# main.net
KiCad netlist of a schematic drawn in Altium Designer
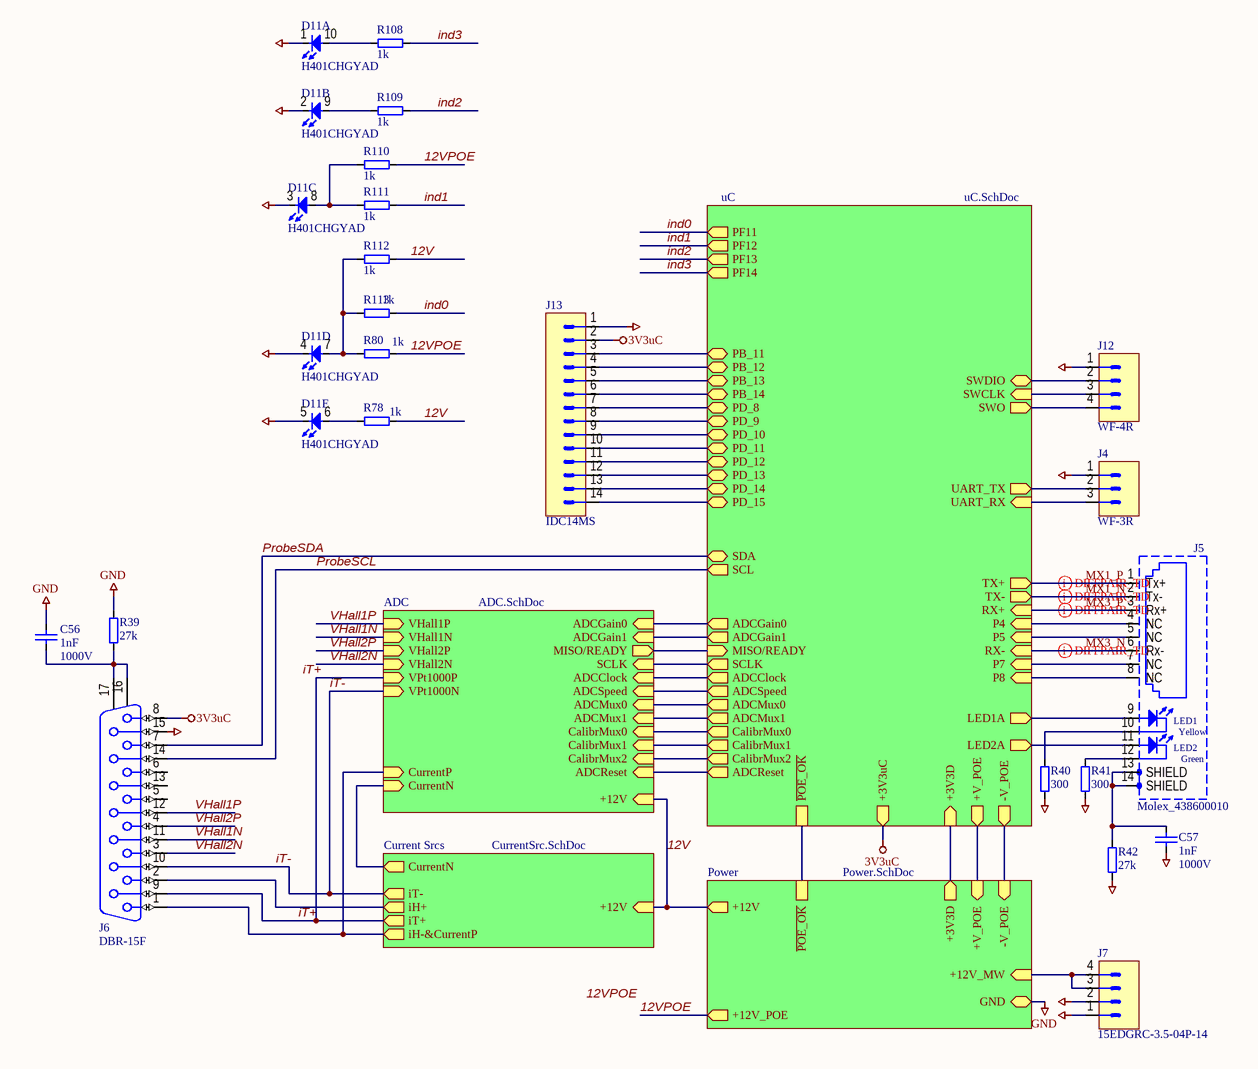
[diagram p0: main.SchDoc]

(export (version "E")
  (design (tool "Eeschema 10.0.6"))
  (components
    (comp (ref "C56")
      (value "1nF")
      (footprint "CAPC1206")
      (description "Чип конденсатор 1206")
      (fields (field (name "VOLTAGE") "1000V") (field (name "TOLERANCE") "1%"))
      (libsource (lib "DDSintLib") (part "C1206"))
    )
    (comp (ref "C57")
      (value "1nF")
      (footprint "CAPC1206")
      (description "Чип конденсатор 1206")
      (fields (field (name "VOLTAGE") "1000V") (field (name "TOLERANCE") "1%"))
      (libsource (lib "DDSintLib") (part "C1206"))
    )
    (comp (ref "D11")
      (value "H401CHGYAD")
      (footprint "H401CHGYAD_LED_CB")
      (description "4LEDs сборка")
      (libsource (lib "DDSintLib") (part "H401CHGYAD"))
    )
    (comp (ref "J4")
      (value "WF-3R")
      (footprint "MOLEX_22-05-7038")
      (description "Вилка  WF3 угловая")
      (libsource (lib "DDSintLib") (part "WF3R"))
    )
    (comp (ref "J5")
      (value "Molex_438600010")
      (footprint "Molex-43860-0010")
      (description "1 Port, 8 Positions, CAT5 RJ45 Modular Connector With Yellow And Green fibers for LEDs")
      (libsource (lib "DDSintLib") (part "Molex_438600010"))
    )
    (comp (ref "J6")
      (value "DBR-15F")
      (footprint "AMPHENOL_L717DFA15S1ATN")
      (description "Вилка  DSUB 9 угловая")
      (libsource (lib "DDS1") (part "D_SUB_15F"))
    )
    (comp (ref "J7")
      (value "15EDGRC-3.5-04P-14")
      (footprint "TE_284512-4")
      (description "Вилка  WF4")
      (libsource (lib "DDSintLib") (part "15EDGRC-3.5-04P-14"))
    )
    (comp (ref "J12")
      (value "WF-4R")
      (footprint "MOLEX_WF4-angle")
      (description "Вилка  WF4 угловая")
      (libsource (lib "DDS1") (part "WF4R"))
    )
    (comp (ref "J13")
      (value "IDC14MS")
      (footprint "3M_2514-6002RB")
      (description "Вилка  14конт., шаг: 2.54мм")
      (libsource (lib "DDS1") (part "IDC14MS"))
    )
    (comp (ref "R39")
      (value "27k")
      (footprint "SMD0805RES")
      (description "Чип резистор 0805")
      (fields (field (name "TOLERANCE") "1%"))
      (libsource (lib "DDSintLib") (part "R0805"))
    )
    (comp (ref "R40")
      (value "300")
      (footprint "RESC1608X64N")
      (description "Чип резистор 0603")
      (fields (field (name "TOLERANCE") "1%"))
      (libsource (lib "DDSintLib") (part "R0603"))
    )
    (comp (ref "R41")
      (value "300")
      (footprint "RESC1608X64N")
      (description "Чип резистор 0603")
      (fields (field (name "TOLERANCE") "1%"))
      (libsource (lib "DDSintLib") (part "R0603"))
    )
    (comp (ref "R42")
      (value "27k")
      (footprint "SMD0805RES")
      (description "Чип резистор 0805")
      (fields (field (name "TOLERANCE") "1%"))
      (libsource (lib "DDSintLib") (part "R0805"))
    )
    (comp (ref "R78")
      (value "1k")
      (footprint "SMD0805RES")
      (description "Чип резистор 0805")
      (fields (field (name "TOLERANCE") "1%"))
      (libsource (lib "DDSintLib") (part "R0805"))
    )
    (comp (ref "R80")
      (value "1k")
      (footprint "SMD0805RES")
      (description "Чип резистор 0805")
      (fields (field (name "TOLERANCE") "1%"))
      (libsource (lib "DDSintLib") (part "R0805"))
    )
    (comp (ref "R108")
      (value "1k")
      (footprint "SMD0805RES")
      (description "Чип резистор 0805")
      (fields (field (name "TOLERANCE") "1%"))
      (libsource (lib "DDSintLib") (part "R0805"))
    )
    (comp (ref "R109")
      (value "1k")
      (footprint "SMD0805RES")
      (description "Чип резистор 0805")
      (fields (field (name "TOLERANCE") "1%"))
      (libsource (lib "DDSintLib") (part "R0805"))
    )
    (comp (ref "R110")
      (value "1k")
      (footprint "SMD0805RES")
      (description "Чип резистор 0805")
      (fields (field (name "TOLERANCE") "1%"))
      (libsource (lib "DDSintLib") (part "R0805"))
    )
    (comp (ref "R111")
      (value "1k")
      (footprint "SMD0805RES")
      (description "Чип резистор 0805")
      (fields (field (name "TOLERANCE") "1%"))
      (libsource (lib "DDSintLib") (part "R0805"))
    )
    (comp (ref "R112")
      (value "1k")
      (footprint "SMD0805RES")
      (description "Чип резистор 0805")
      (fields (field (name "TOLERANCE") "1%"))
      (libsource (lib "DDSintLib") (part "R0805"))
    )
    (comp (ref "R113")
      (value "1k")
      (footprint "SMD0805RES")
      (description "Чип резистор 0805")
      (fields (field (name "TOLERANCE") "1%"))
      (libsource (lib "DDSintLib") (part "R0805"))
    )
  )
  (nets
    (net (code "2") (name "/+12V_MW") (class "Default")
      (node (ref "J7") (pin "3") (pinfunction "3_3") (pintype "bidirectional"))
      (node (ref "J7") (pin "4") (pinfunction "4_4") (pintype "bidirectional"))
    )
    (net (code "5") (name "/12V") (class "Default")
      (node (ref "R112") (pin "2") (pinfunction "2_2") (pintype "passive"))
      (node (ref "R78") (pin "2") (pinfunction "2_2") (pintype "passive"))
    )
    (net (code "6") (name "/12VPOE") (class "Default")
      (node (ref "R110") (pin "2") (pinfunction "2_2") (pintype "passive"))
      (node (ref "R80") (pin "2") (pinfunction "2_2") (pintype "passive"))
    )
    (net (code "18") (name "/LED1A") (class "Default")
      (node (ref "J5") (pin "9") (pinfunction "ALED1_9") (pintype "passive"))
    )
    (net (code "19") (name "/LED2A") (class "Default")
      (node (ref "J5") (pin "11") (pinfunction "ALED2_11") (pintype "passive"))
    )
    (net (code "21") (name "/MX1_N") (class "Default")
      (node (ref "J5") (pin "2") (pinfunction "Tx-_2") (pintype "bidirectional"))
    )
    (net (code "22") (name "/MX1_P") (class "Default")
      (node (ref "J5") (pin "1") (pinfunction "Tx+_1") (pintype "bidirectional"))
    )
    (net (code "23") (name "/MX3_N") (class "Default")
      (node (ref "J5") (pin "6") (pinfunction "Rx-_6") (pintype "bidirectional"))
    )
    (net (code "24") (name "/MX3_P") (class "Default")
      (node (ref "J5") (pin "3") (pinfunction "Rx+_3") (pintype "bidirectional"))
    )
    (net (code "25") (name "/P4") (class "Default")
      (node (ref "J5") (pin "4") (pinfunction "NC_4") (pintype "bidirectional"))
    )
    (net (code "26") (name "/P5") (class "Default")
      (node (ref "J5") (pin "5") (pinfunction "NC_5") (pintype "bidirectional"))
    )
    (net (code "27") (name "/P7") (class "Default")
      (node (ref "J5") (pin "7") (pinfunction "NC_7") (pintype "bidirectional"))
    )
    (net (code "28") (name "/P8") (class "Default")
      (node (ref "J5") (pin "8") (pinfunction "NC_8") (pintype "bidirectional"))
    )
    (net (code "29") (name "/PB_11") (class "Default")
      (node (ref "J13") (pin "3") (pinfunction "3_3") (pintype "bidirectional"))
    )
    (net (code "30") (name "/PB_12") (class "Default")
      (node (ref "J13") (pin "4") (pinfunction "4_4") (pintype "bidirectional"))
    )
    (net (code "31") (name "/PB_13") (class "Default")
      (node (ref "J13") (pin "5") (pinfunction "5_5") (pintype "bidirectional"))
    )
    (net (code "32") (name "/PB_14") (class "Default")
      (node (ref "J13") (pin "6") (pinfunction "6_6") (pintype "bidirectional"))
    )
    (net (code "33") (name "/PD_8") (class "Default")
      (node (ref "J13") (pin "7") (pinfunction "7_7") (pintype "bidirectional"))
    )
    (net (code "34") (name "/PD_9") (class "Default")
      (node (ref "J13") (pin "8") (pinfunction "8_8") (pintype "bidirectional"))
    )
    (net (code "35") (name "/PD_10") (class "Default")
      (node (ref "J13") (pin "9") (pinfunction "9_9") (pintype "bidirectional"))
    )
    (net (code "36") (name "/PD_11") (class "Default")
      (node (ref "J13") (pin "10") (pinfunction "10_10") (pintype "bidirectional"))
    )
    (net (code "37") (name "/PD_12") (class "Default")
      (node (ref "J13") (pin "11") (pinfunction "11_11") (pintype "bidirectional"))
    )
    (net (code "38") (name "/PD_13") (class "Default")
      (node (ref "J13") (pin "12") (pinfunction "12_12") (pintype "bidirectional"))
    )
    (net (code "39") (name "/PD_14") (class "Default")
      (node (ref "J13") (pin "13") (pinfunction "13_13") (pintype "bidirectional"))
    )
    (net (code "40") (name "/PD_15") (class "Default")
      (node (ref "J13") (pin "14") (pinfunction "14_14") (pintype "bidirectional"))
    )
    (net (code "42") (name "/ProbeSCL") (class "Default")
      (node (ref "J6") (pin "14") (pinfunction "14_14") (pintype "bidirectional"))
    )
    (net (code "43") (name "/ProbeSDA") (class "Default")
      (node (ref "J6") (pin "7") (pinfunction "7_7") (pintype "bidirectional"))
    )
    (net (code "45") (name "/SWCLK") (class "Default")
      (node (ref "J12") (pin "3") (pinfunction "3_3") (pintype "bidirectional"))
    )
    (net (code "46") (name "/SWDIO") (class "Default")
      (node (ref "J12") (pin "2") (pinfunction "2_2") (pintype "bidirectional"))
    )
    (net (code "47") (name "/SWO") (class "Default")
      (node (ref "J12") (pin "4") (pinfunction "4_4") (pintype "bidirectional"))
    )
    (net (code "48") (name "/UART_RX") (class "Default")
      (node (ref "J4") (pin "3") (pinfunction "3_3") (pintype "bidirectional"))
    )
    (net (code "49") (name "/UART_TX") (class "Default")
      (node (ref "J4") (pin "2") (pinfunction "2_2") (pintype "bidirectional"))
    )
    (net (code "50") (name "/VHall1N") (class "Default")
      (node (ref "J6") (pin "11") (pinfunction "11_11") (pintype "bidirectional"))
    )
    (net (code "51") (name "/VHall1P") (class "Default")
      (node (ref "J6") (pin "12") (pinfunction "12_12") (pintype "bidirectional"))
    )
    (net (code "52") (name "/VHall2N") (class "Default")
      (node (ref "J6") (pin "3") (pinfunction "3_3") (pintype "bidirectional"))
    )
    (net (code "53") (name "/VHall2P") (class "Default")
      (node (ref "J6") (pin "4") (pinfunction "4_4") (pintype "bidirectional"))
    )
    (net (code "54") (name "/iH+") (class "Default")
      (node (ref "J6") (pin "2") (pinfunction "2_2") (pintype "bidirectional"))
    )
    (net (code "55") (name "/iH-&CurrentP") (class "Default")
      (node (ref "J6") (pin "1") (pinfunction "1_1") (pintype "bidirectional"))
    )
    (net (code "56") (name "/iT+") (class "Default")
      (node (ref "J6") (pin "9") (pinfunction "9_9") (pintype "bidirectional"))
    )
    (net (code "57") (name "/iT-") (class "Default")
      (node (ref "J6") (pin "10") (pinfunction "10_10") (pintype "bidirectional"))
    )
    (net (code "58") (name "/ind0") (class "Default")
      (node (ref "R113") (pin "2") (pinfunction "2_2") (pintype "passive"))
    )
    (net (code "59") (name "/ind1") (class "Default")
      (node (ref "R111") (pin "2") (pinfunction "2_2") (pintype "passive"))
    )
    (net (code "60") (name "/ind2") (class "Default")
      (node (ref "R109") (pin "2") (pinfunction "2_2") (pintype "passive"))
    )
    (net (code "61") (name "/ind3") (class "Default")
      (node (ref "R108") (pin "2") (pinfunction "2_2") (pintype "passive"))
    )
    (net (code "62") (name "3V3uC") (class "Default")
      (node (ref "J13") (pin "2") (pinfunction "2_2") (pintype "bidirectional"))
      (node (ref "J6") (pin "8") (pinfunction "8_8") (pintype "bidirectional"))
    )
    (net (code "63") (name "GND") (class "Default")
      (node (ref "C56") (pin "1") (pinfunction "1_1") (pintype "passive"))
      (node (ref "C57") (pin "1") (pinfunction "1_1") (pintype "passive"))
      (node (ref "D11") (pin "1") (pinfunction "C1_1") (pintype "passive"))
      (node (ref "D11") (pin "2") (pinfunction "C2_2") (pintype "passive"))
      (node (ref "D11") (pin "3") (pinfunction "C3_3") (pintype "passive"))
      (node (ref "D11") (pin "4") (pinfunction "C4_4") (pintype "passive"))
      (node (ref "D11") (pin "5") (pinfunction "C5_5") (pintype "passive"))
      (node (ref "J12") (pin "1") (pinfunction "1_1") (pintype "bidirectional"))
      (node (ref "J13") (pin "1") (pinfunction "1_1") (pintype "bidirectional"))
      (node (ref "J4") (pin "1") (pinfunction "1_1") (pintype "bidirectional"))
      (node (ref "J6") (pin "15") (pinfunction "15_15") (pintype "bidirectional"))
      (node (ref "J7") (pin "1") (pinfunction "1_1") (pintype "bidirectional"))
      (node (ref "J7") (pin "2") (pinfunction "2_2") (pintype "bidirectional"))
      (node (ref "R39") (pin "2") (pinfunction "2_2") (pintype "passive"))
      (node (ref "R40") (pin "1") (pinfunction "1_1") (pintype "passive"))
      (node (ref "R41") (pin "1") (pinfunction "1_1") (pintype "passive"))
      (node (ref "R42") (pin "1") (pinfunction "1_1") (pintype "passive"))
    )
    (net (code "64") (name "Net-(C56-Pad2)") (class "Default")
      (node (ref "C56") (pin "2") (pinfunction "2_2") (pintype "passive"))
      (node (ref "J6") (pin "16") (pinfunction "16_16") (pintype "passive"))
      (node (ref "J6") (pin "17") (pinfunction "17_17") (pintype "passive"))
      (node (ref "R39") (pin "1") (pinfunction "1_1") (pintype "passive"))
    )
    (net (code "65") (name "Net-(C57-Pad2)") (class "Default")
      (node (ref "C57") (pin "2") (pinfunction "2_2") (pintype "passive"))
      (node (ref "J5") (pin "13") (pinfunction "SHIELD_13") (pintype "passive"))
      (node (ref "J5") (pin "14") (pinfunction "SHIELD_14") (pintype "passive"))
      (node (ref "R42") (pin "2") (pinfunction "2_2") (pintype "passive"))
    )
    (net (code "66") (name "Net-(D11A-A1)") (class "Default")
      (node (ref "D11") (pin "10") (pinfunction "A1_10") (pintype "passive"))
      (node (ref "R108") (pin "1") (pinfunction "1_1") (pintype "passive"))
    )
    (net (code "67") (name "Net-(D11B-A2)") (class "Default")
      (node (ref "D11") (pin "9") (pinfunction "A2_9") (pintype "passive"))
      (node (ref "R109") (pin "1") (pinfunction "1_1") (pintype "passive"))
    )
    (net (code "68") (name "Net-(D11C-A3)") (class "Default")
      (node (ref "D11") (pin "8") (pinfunction "A3_8") (pintype "passive"))
      (node (ref "R110") (pin "1") (pinfunction "1_1") (pintype "passive"))
      (node (ref "R111") (pin "1") (pinfunction "1_1") (pintype "passive"))
    )
    (net (code "69") (name "Net-(D11D-A4)") (class "Default")
      (node (ref "D11") (pin "7") (pinfunction "A4_7") (pintype "passive"))
      (node (ref "R112") (pin "1") (pinfunction "1_1") (pintype "passive"))
      (node (ref "R113") (pin "1") (pinfunction "1_1") (pintype "passive"))
      (node (ref "R80") (pin "1") (pinfunction "1_1") (pintype "passive"))
    )
    (net (code "70") (name "Net-(D11E-A5)") (class "Default")
      (node (ref "D11") (pin "6") (pinfunction "A5_6") (pintype "passive"))
      (node (ref "R78") (pin "1") (pinfunction "1_1") (pintype "passive"))
    )
    (net (code "71") (name "Net-(J5-CLED1)") (class "Default")
      (node (ref "J5") (pin "10") (pinfunction "CLED1_10") (pintype "passive"))
      (node (ref "R40") (pin "2") (pinfunction "2_2") (pintype "passive"))
    )
    (net (code "72") (name "Net-(J5-CLED2)") (class "Default")
      (node (ref "J5") (pin "12") (pinfunction "CLED2_12") (pintype "passive"))
      (node (ref "R41") (pin "2") (pinfunction "2_2") (pintype "passive"))
    )
    (net (code "73") (name "unconnected-(J6-Pad5)") (class "Default")
      (node (ref "J6") (pin "5") (pinfunction "5_5") (pintype "bidirectional"))
    )
    (net (code "74") (name "unconnected-(J6-Pad6)") (class "Default")
      (node (ref "J6") (pin "6") (pinfunction "6_6") (pintype "bidirectional"))
    )
    (net (code "75") (name "unconnected-(J6-Pad13)") (class "Default")
      (node (ref "J6") (pin "13") (pinfunction "13_13") (pintype "bidirectional"))
    )
  )
)
